# Pair_1.net
KiCad netlist of a schematic drawn in Altium Designer
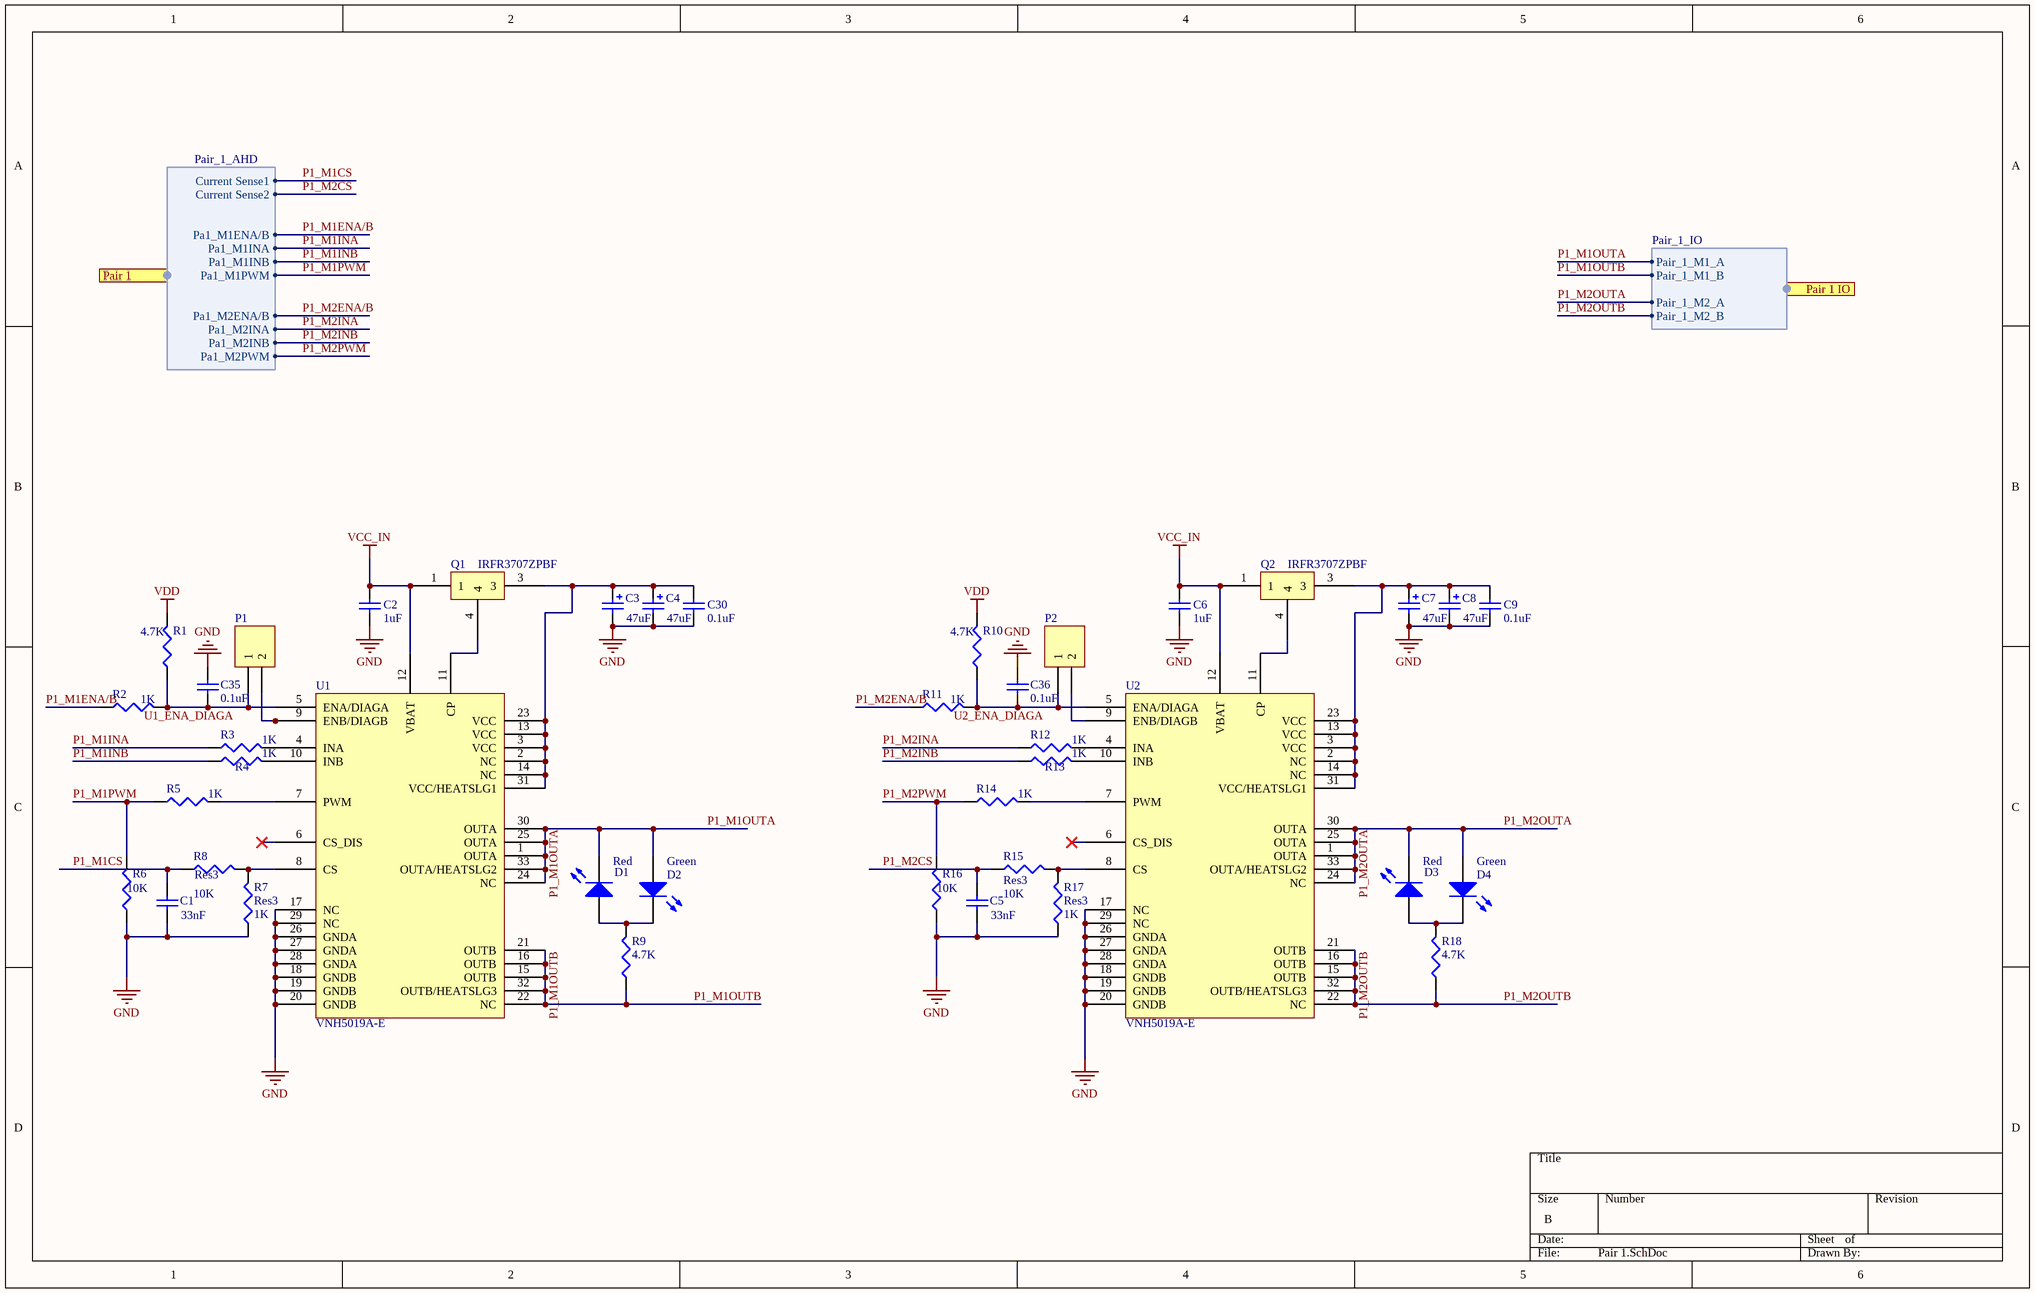
[diagram p0: Pair 1.SchDoc]

(export (version "E")
  (design (tool "Eeschema 10.0.6"))
  (components
    (comp (ref "C1")
      (value "33nF")
      (footprint "1608[0603]")
      (description "Capacitor (Semiconductor SIM Model)")
      (fields (field (name "Comment") "Cap Semi") (field (name "PUBLISHER") "Altium Limited"))
      (libsource (lib "Miscellaneous Devices") (part "Cap Semi"))
    )
    (comp (ref "C2")
      (value "1uF")
      (footprint "1608[0603]")
      (description "Capacitor (Semiconductor SIM Model)")
      (fields (field (name "Comment") "Cap Semi") (field (name "PUBLISHER") "Altium Limited"))
      (libsource (lib "Miscellaneous Devices") (part "Cap Semi"))
    )
    (comp (ref "C3")
      (value "47uF")
      (footprint "CAPPR2-5x6.8")
      (description "Polarized Capacitor (Axial)")
      (fields (field (name "Comment") "Cap Pol2") (field (name "PUBLISHER") "Altium Limited"))
      (libsource (lib "Miscellaneous Devices") (part "Cap Pol2"))
    )
    (comp (ref "C4")
      (value "47uF")
      (footprint "CAPPR2-5x6.8")
      (description "Polarized Capacitor (Axial)")
      (fields (field (name "Comment") "Cap Pol2") (field (name "PUBLISHER") "Altium Limited"))
      (libsource (lib "Miscellaneous Devices") (part "Cap Pol2"))
    )
    (comp (ref "C5")
      (value "33nF")
      (footprint "1608[0603]")
      (description "Capacitor (Semiconductor SIM Model)")
      (fields (field (name "Comment") "Cap Semi") (field (name "PUBLISHER") "Altium Limited"))
      (libsource (lib "Miscellaneous Devices") (part "Cap Semi"))
    )
    (comp (ref "C6")
      (value "1uF")
      (footprint "1608[0603]")
      (description "Capacitor (Semiconductor SIM Model)")
      (fields (field (name "Comment") "Cap Semi") (field (name "PUBLISHER") "Altium Limited"))
      (libsource (lib "Miscellaneous Devices") (part "Cap Semi"))
    )
    (comp (ref "C7")
      (value "47uF")
      (footprint "CAPPR2-5x6.8")
      (description "Polarized Capacitor (Axial)")
      (fields (field (name "Comment") "Cap Pol2") (field (name "PUBLISHER") "Altium Limited"))
      (libsource (lib "Miscellaneous Devices") (part "Cap Pol2"))
    )
    (comp (ref "C8")
      (value "47uF")
      (footprint "CAPPR2-5x6.8")
      (description "Polarized Capacitor (Axial)")
      (fields (field (name "Comment") "Cap Pol2") (field (name "PUBLISHER") "Altium Limited"))
      (libsource (lib "Miscellaneous Devices") (part "Cap Pol2"))
    )
    (comp (ref "C9")
      (value "0.1uF")
      (footprint "C1206")
      (description "Capacitor (Semiconductor SIM Model)")
      (fields (field (name "Comment") "Cap Semi") (field (name "PUBLISHER") "Altium Limited"))
      (libsource (lib "Miscellaneous Devices") (part "Cap Semi"))
    )
    (comp (ref "C30")
      (value "0.1uF")
      (footprint "C1206")
      (description "Capacitor (Semiconductor SIM Model)")
      (fields (field (name "Comment") "Cap Semi") (field (name "PUBLISHER") "Altium Limited"))
      (libsource (lib "Miscellaneous Devices") (part "Cap Semi"))
    )
    (comp (ref "C35")
      (value "0.1uF")
      (footprint "1608[0603]")
      (description "Capacitor (Semiconductor SIM Model)")
      (fields (field (name "Comment") "Cap Semi") (field (name "PUBLISHER") "Altium Limited"))
      (libsource (lib "Miscellaneous Devices") (part "Cap Semi"))
    )
    (comp (ref "C36")
      (value "0.1uF")
      (footprint "1608[0603]")
      (description "Capacitor (Semiconductor SIM Model)")
      (fields (field (name "Comment") "Cap Semi") (field (name "PUBLISHER") "Altium Limited"))
      (libsource (lib "Miscellaneous Devices") (part "Cap Semi"))
    )
    (comp (ref "D1")
      (value "LED2")
      (footprint "3.2X1.6X1.1")
      (description "Typical RED, GREEN, YELLOW, AMBER GaAs LED")
      (fields (field (name "PUBLISHER") "Altium Limited"))
      (libsource (lib "Miscellaneous Devices") (part "LED2"))
    )
    (comp (ref "D2")
      (value "LED2")
      (footprint "3.2X1.6X1.1")
      (description "Typical RED, GREEN, YELLOW, AMBER GaAs LED")
      (fields (field (name "PUBLISHER") "Altium Limited"))
      (libsource (lib "Miscellaneous Devices") (part "LED2"))
    )
    (comp (ref "D3")
      (value "LED2")
      (footprint "3.2X1.6X1.1")
      (description "Typical RED, GREEN, YELLOW, AMBER GaAs LED")
      (fields (field (name "PUBLISHER") "Altium Limited"))
      (libsource (lib "Miscellaneous Devices") (part "LED2"))
    )
    (comp (ref "D4")
      (value "LED2")
      (footprint "3.2X1.6X1.1")
      (description "Typical RED, GREEN, YELLOW, AMBER GaAs LED")
      (fields (field (name "PUBLISHER") "Altium Limited"))
      (libsource (lib "Miscellaneous Devices") (part "LED2"))
    )
    (comp (ref "P1")
      (value "Header 2")
      (footprint "HDR1X2")
      (description "Header, 2-Pin")
      (fields (field (name "PUBLISHER") "Altium Limited"))
      (libsource (lib "Miscellaneous Connectors") (part "Header 2"))
    )
    (comp (ref "P2")
      (value "Header 2")
      (footprint "HDR1X2")
      (description "Header, 2-Pin")
      (fields (field (name "PUBLISHER") "Altium Limited"))
      (libsource (lib "Miscellaneous Connectors") (part "Header 2"))
    )
    (comp (ref "Q1")
      (value "IRFR3707ZPBF")
      (footprint "IRFR3707ZPBF")
      (description "Power FET")
      (libsource (lib "Thruster Shield Part Library") (part "IRFR3707ZPBF"))
    )
    (comp (ref "Q2")
      (value "IRFR3707ZPBF")
      (footprint "IRFR3707ZPBF")
      (description "Power FET")
      (libsource (lib "Thruster Shield Part Library") (part "IRFR3707ZPBF"))
    )
    (comp (ref "R1")
      (value "4.7K")
      (footprint "RESC1608L")
      (description "Resistor")
      (fields (field (name "Comment") "Res3") (field (name "PUBLISHER") "Altium Limited"))
      (libsource (lib "Miscellaneous Devices") (part "Res3"))
    )
    (comp (ref "R2")
      (value "1K")
      (footprint "RESC1608L")
      (description "Resistor")
      (fields (field (name "Comment") "Res3") (field (name "PUBLISHER") "Altium Limited"))
      (libsource (lib "Miscellaneous Devices") (part "Res3"))
    )
    (comp (ref "R3")
      (value "1K")
      (footprint "RESC1608L")
      (description "Resistor")
      (fields (field (name "Comment") "Res3") (field (name "PUBLISHER") "Altium Limited"))
      (libsource (lib "Miscellaneous Devices") (part "Res3"))
    )
    (comp (ref "R4")
      (value "1K")
      (footprint "RESC1608L")
      (description "Resistor")
      (fields (field (name "Comment") "Res3") (field (name "PUBLISHER") "Altium Limited"))
      (libsource (lib "Miscellaneous Devices") (part "Res3"))
    )
    (comp (ref "R5")
      (value "1K")
      (footprint "RESC1608L")
      (description "Resistor")
      (fields (field (name "Comment") "Res3") (field (name "PUBLISHER") "Altium Limited"))
      (libsource (lib "Miscellaneous Devices") (part "Res3"))
    )
    (comp (ref "R6")
      (value "10K")
      (footprint "RESC1608L")
      (description "Resistor")
      (fields (field (name "Comment") "Res3") (field (name "PUBLISHER") "Altium Limited"))
      (libsource (lib "Miscellaneous Devices") (part "Res3"))
    )
    (comp (ref "R7")
      (value "Res3")
      (footprint "RESC1608L")
      (description "Resistor")
      (fields (field (name "ALTIUM_VALUE") "1K") (field (name "PUBLISHER") "Altium Limited"))
      (libsource (lib "Miscellaneous Devices") (part "Res3"))
    )
    (comp (ref "R8")
      (value "Res3")
      (footprint "RESC1608L")
      (description "Resistor")
      (fields (field (name "ALTIUM_VALUE") "10K") (field (name "PUBLISHER") "Altium Limited"))
      (libsource (lib "Miscellaneous Devices") (part "Res3"))
    )
    (comp (ref "R9")
      (value "4.7K")
      (footprint "0805 SMD Resistor")
      (description "Resistor")
      (fields (field (name "Comment") "Res3") (field (name "PUBLISHER") "Altium Limited"))
      (libsource (lib "Miscellaneous Devices") (part "Res3"))
    )
    (comp (ref "R10")
      (value "4.7K")
      (footprint "RESC1608L")
      (description "Resistor")
      (fields (field (name "Comment") "Res3") (field (name "PUBLISHER") "Altium Limited"))
      (libsource (lib "Miscellaneous Devices") (part "Res3"))
    )
    (comp (ref "R11")
      (value "1K")
      (footprint "RESC1608L")
      (description "Resistor")
      (fields (field (name "Comment") "Res3") (field (name "PUBLISHER") "Altium Limited"))
      (libsource (lib "Miscellaneous Devices") (part "Res3"))
    )
    (comp (ref "R12")
      (value "1K")
      (footprint "RESC1608L")
      (description "Resistor")
      (fields (field (name "Comment") "Res3") (field (name "PUBLISHER") "Altium Limited"))
      (libsource (lib "Miscellaneous Devices") (part "Res3"))
    )
    (comp (ref "R13")
      (value "1K")
      (footprint "RESC1608L")
      (description "Resistor")
      (fields (field (name "Comment") "Res3") (field (name "PUBLISHER") "Altium Limited"))
      (libsource (lib "Miscellaneous Devices") (part "Res3"))
    )
    (comp (ref "R14")
      (value "1K")
      (footprint "RESC1608L")
      (description "Resistor")
      (fields (field (name "Comment") "Res3") (field (name "PUBLISHER") "Altium Limited"))
      (libsource (lib "Miscellaneous Devices") (part "Res3"))
    )
    (comp (ref "R15")
      (value "Res3")
      (footprint "RESC1608L")
      (description "Resistor")
      (fields (field (name "ALTIUM_VALUE") "10K") (field (name "PUBLISHER") "Altium Limited"))
      (libsource (lib "Miscellaneous Devices") (part "Res3"))
    )
    (comp (ref "R16")
      (value "10K")
      (footprint "RESC1608L")
      (description "Resistor")
      (fields (field (name "Comment") "Res3") (field (name "PUBLISHER") "Altium Limited"))
      (libsource (lib "Miscellaneous Devices") (part "Res3"))
    )
    (comp (ref "R17")
      (value "Res3")
      (footprint "RESC1608L")
      (description "Resistor")
      (fields (field (name "ALTIUM_VALUE") "1K") (field (name "PUBLISHER") "Altium Limited"))
      (libsource (lib "Miscellaneous Devices") (part "Res3"))
    )
    (comp (ref "R18")
      (value "4.7K")
      (footprint "0805 SMD Resistor")
      (description "Resistor")
      (fields (field (name "Comment") "Res3") (field (name "PUBLISHER") "Altium Limited"))
      (libsource (lib "Miscellaneous Devices") (part "Res3"))
    )
    (comp (ref "U1")
      (value "VNH5019A-E")
      (footprint "VNH5019A-E")
      (description "VNH5019A-E H-Bridge")
      (libsource (lib "Thruster Shield Part Library") (part "VNH5019A-E"))
    )
    (comp (ref "U2")
      (value "VNH5019A-E")
      (footprint "VNH5019A-E")
      (description "VNH5019A-E H-Bridge")
      (libsource (lib "Thruster Shield Part Library") (part "VNH5019A-E"))
    )
  )
  (nets
    (net (code "3") (name "/P1_M1CS") (class "Default")
      (node (ref "C1") (pin "2") (pinfunction "2_2") (pintype "passive"))
      (node (ref "R8") (pin "1") (pinfunction "1_1") (pintype "passive"))
    )
    (net (code "4") (name "/P1_M1ENA{slash}B") (class "Default")
      (node (ref "R2") (pin "1") (pinfunction "1_1") (pintype "passive"))
    )
    (net (code "5") (name "/P1_M1INA") (class "Default")
      (node (ref "R3") (pin "1") (pinfunction "1_1") (pintype "passive"))
    )
    (net (code "6") (name "/P1_M1INB") (class "Default")
      (node (ref "R4") (pin "1") (pinfunction "1_1") (pintype "passive"))
    )
    (net (code "7") (name "/P1_M1OUTA") (class "Default")
      (node (ref "D1") (pin "2") (pinfunction "K_2") (pintype "passive"))
      (node (ref "D2") (pin "1") (pinfunction "A_1") (pintype "passive"))
      (node (ref "U1") (pin "1") (pinfunction "OUTA_1") (pintype "passive"))
      (node (ref "U1") (pin "24") (pinfunction "NC_24") (pintype "passive"))
      (node (ref "U1") (pin "25") (pinfunction "OUTA_25") (pintype "passive"))
      (node (ref "U1") (pin "30") (pinfunction "OUTA_30") (pintype "passive"))
      (node (ref "U1") (pin "33") (pinfunction "OUTA/HEATSLG2_33") (pintype "passive"))
    )
    (net (code "8") (name "/P1_M1OUTB") (class "Default")
      (node (ref "R9") (pin "1") (pinfunction "1_1") (pintype "passive"))
      (node (ref "U1") (pin "15") (pinfunction "OUTB_15") (pintype "passive"))
      (node (ref "U1") (pin "16") (pinfunction "OUTB_16") (pintype "passive"))
      (node (ref "U1") (pin "21") (pinfunction "OUTB_21") (pintype "passive"))
      (node (ref "U1") (pin "22") (pinfunction "NC_22") (pintype "passive"))
      (node (ref "U1") (pin "32") (pinfunction "OUTB/HEATSLG3_32") (pintype "passive"))
    )
    (net (code "9") (name "/P1_M1PWM") (class "Default")
      (node (ref "R5") (pin "1") (pinfunction "1_1") (pintype "passive"))
      (node (ref "R6") (pin "2") (pinfunction "2_2") (pintype "passive"))
    )
    (net (code "10") (name "/P1_M2CS") (class "Default")
      (node (ref "C5") (pin "2") (pinfunction "2_2") (pintype "passive"))
      (node (ref "R15") (pin "1") (pinfunction "1_1") (pintype "passive"))
    )
    (net (code "11") (name "/P1_M2ENA{slash}B") (class "Default")
      (node (ref "R11") (pin "1") (pinfunction "1_1") (pintype "passive"))
    )
    (net (code "12") (name "/P1_M2INA") (class "Default")
      (node (ref "R12") (pin "1") (pinfunction "1_1") (pintype "passive"))
    )
    (net (code "13") (name "/P1_M2INB") (class "Default")
      (node (ref "R13") (pin "1") (pinfunction "1_1") (pintype "passive"))
    )
    (net (code "14") (name "/P1_M2OUTA") (class "Default")
      (node (ref "D3") (pin "2") (pinfunction "K_2") (pintype "passive"))
      (node (ref "D4") (pin "1") (pinfunction "A_1") (pintype "passive"))
      (node (ref "U2") (pin "1") (pinfunction "OUTA_1") (pintype "passive"))
      (node (ref "U2") (pin "24") (pinfunction "NC_24") (pintype "passive"))
      (node (ref "U2") (pin "25") (pinfunction "OUTA_25") (pintype "passive"))
      (node (ref "U2") (pin "30") (pinfunction "OUTA_30") (pintype "passive"))
      (node (ref "U2") (pin "33") (pinfunction "OUTA/HEATSLG2_33") (pintype "passive"))
    )
    (net (code "15") (name "/P1_M2OUTB") (class "Default")
      (node (ref "R18") (pin "1") (pinfunction "1_1") (pintype "passive"))
      (node (ref "U2") (pin "15") (pinfunction "OUTB_15") (pintype "passive"))
      (node (ref "U2") (pin "16") (pinfunction "OUTB_16") (pintype "passive"))
      (node (ref "U2") (pin "21") (pinfunction "OUTB_21") (pintype "passive"))
      (node (ref "U2") (pin "22") (pinfunction "NC_22") (pintype "passive"))
      (node (ref "U2") (pin "32") (pinfunction "OUTB/HEATSLG3_32") (pintype "passive"))
    )
    (net (code "16") (name "/P1_M2PWM") (class "Default")
      (node (ref "R14") (pin "1") (pinfunction "1_1") (pintype "passive"))
      (node (ref "R16") (pin "2") (pinfunction "2_2") (pintype "passive"))
    )
    (net (code "17") (name "/U1_ENA_DIAGA") (class "Default")
      (node (ref "C35") (pin "2") (pinfunction "2_2") (pintype "passive"))
      (node (ref "P1") (pin "1") (pinfunction "1_1") (pintype "passive"))
      (node (ref "R1") (pin "1") (pinfunction "1_1") (pintype "passive"))
      (node (ref "R2") (pin "2") (pinfunction "2_2") (pintype "passive"))
      (node (ref "U1") (pin "5") (pinfunction "ENA/DIAGA_5") (pintype "passive"))
    )
    (net (code "18") (name "/U2_ENA_DIAGA") (class "Default")
      (node (ref "C36") (pin "2") (pinfunction "2_2") (pintype "passive"))
      (node (ref "P2") (pin "1") (pinfunction "1_1") (pintype "passive"))
      (node (ref "R10") (pin "1") (pinfunction "1_1") (pintype "passive"))
      (node (ref "R11") (pin "2") (pinfunction "2_2") (pintype "passive"))
      (node (ref "U2") (pin "5") (pinfunction "ENA/DIAGA_5") (pintype "passive"))
    )
    (net (code "21") (name "GND") (class "Default")
      (node (ref "C1") (pin "1") (pinfunction "1_1") (pintype "passive"))
      (node (ref "C2") (pin "1") (pinfunction "1_1") (pintype "passive"))
      (node (ref "C3") (pin "2") (pinfunction "2_2") (pintype "passive"))
      (node (ref "C30") (pin "1") (pinfunction "1_1") (pintype "passive"))
      (node (ref "C35") (pin "1") (pinfunction "1_1") (pintype "passive"))
      (node (ref "C36") (pin "1") (pinfunction "1_1") (pintype "passive"))
      (node (ref "C4") (pin "2") (pinfunction "2_2") (pintype "passive"))
      (node (ref "C5") (pin "1") (pinfunction "1_1") (pintype "passive"))
      (node (ref "C6") (pin "1") (pinfunction "1_1") (pintype "passive"))
      (node (ref "C7") (pin "2") (pinfunction "2_2") (pintype "passive"))
      (node (ref "C8") (pin "2") (pinfunction "2_2") (pintype "passive"))
      (node (ref "C9") (pin "1") (pinfunction "1_1") (pintype "passive"))
      (node (ref "R16") (pin "1") (pinfunction "1_1") (pintype "passive"))
      (node (ref "R17") (pin "1") (pinfunction "1_1") (pintype "passive"))
      (node (ref "R6") (pin "1") (pinfunction "1_1") (pintype "passive"))
      (node (ref "R7") (pin "1") (pinfunction "1_1") (pintype "passive"))
      (node (ref "U1") (pin "17") (pinfunction "NC_17") (pintype "passive"))
      (node (ref "U1") (pin "18") (pinfunction "GNDB_18") (pintype "passive"))
      (node (ref "U1") (pin "19") (pinfunction "GNDB_19") (pintype "passive"))
      (node (ref "U1") (pin "20") (pinfunction "GNDB_20") (pintype "passive"))
      (node (ref "U1") (pin "26") (pinfunction "GNDA_26") (pintype "passive"))
      (node (ref "U1") (pin "27") (pinfunction "GNDA_27") (pintype "passive"))
      (node (ref "U1") (pin "28") (pinfunction "GNDA_28") (pintype "passive"))
      (node (ref "U1") (pin "29") (pinfunction "NC_29") (pintype "passive"))
      (node (ref "U2") (pin "17") (pinfunction "NC_17") (pintype "passive"))
      (node (ref "U2") (pin "18") (pinfunction "GNDB_18") (pintype "passive"))
      (node (ref "U2") (pin "19") (pinfunction "GNDB_19") (pintype "passive"))
      (node (ref "U2") (pin "20") (pinfunction "GNDB_20") (pintype "passive"))
      (node (ref "U2") (pin "26") (pinfunction "GNDA_26") (pintype "passive"))
      (node (ref "U2") (pin "27") (pinfunction "GNDA_27") (pintype "passive"))
      (node (ref "U2") (pin "28") (pinfunction "GNDA_28") (pintype "passive"))
      (node (ref "U2") (pin "29") (pinfunction "NC_29") (pintype "passive"))
    )
    (net (code "22") (name "Net-(D1-A)") (class "Default")
      (node (ref "D1") (pin "1") (pinfunction "A_1") (pintype "passive"))
      (node (ref "D2") (pin "2") (pinfunction "K_2") (pintype "passive"))
      (node (ref "R9") (pin "2") (pinfunction "2_2") (pintype "passive"))
    )
    (net (code "23") (name "Net-(D3-A)") (class "Default")
      (node (ref "D3") (pin "1") (pinfunction "A_1") (pintype "passive"))
      (node (ref "D4") (pin "2") (pinfunction "K_2") (pintype "passive"))
      (node (ref "R18") (pin "2") (pinfunction "2_2") (pintype "passive"))
    )
    (net (code "24") (name "Net-(U1-CP)") (class "Default")
      (node (ref "Q1") (pin "4") (pinfunction "4_4") (pintype "passive"))
      (node (ref "U1") (pin "11") (pinfunction "CP_11") (pintype "passive"))
    )
    (net (code "25") (name "Net-(U1-CS)") (class "Default")
      (node (ref "R7") (pin "2") (pinfunction "2_2") (pintype "passive"))
      (node (ref "R8") (pin "2") (pinfunction "2_2") (pintype "passive"))
      (node (ref "U1") (pin "8") (pinfunction "CS_8") (pintype "passive"))
    )
    (net (code "26") (name "Net-(U1-ENB{slash}DIAGB)") (class "Default")
      (node (ref "P1") (pin "2") (pinfunction "2_2") (pintype "passive"))
      (node (ref "U1") (pin "9") (pinfunction "ENB/DIAGB_9") (pintype "passive"))
    )
    (net (code "27") (name "Net-(U1-INA)") (class "Default")
      (node (ref "R3") (pin "2") (pinfunction "2_2") (pintype "passive"))
      (node (ref "U1") (pin "4") (pinfunction "INA_4") (pintype "passive"))
    )
    (net (code "28") (name "Net-(U1-INB)") (class "Default")
      (node (ref "R4") (pin "2") (pinfunction "2_2") (pintype "passive"))
      (node (ref "U1") (pin "10") (pinfunction "INB_10") (pintype "passive"))
    )
    (net (code "29") (name "Net-(U1-PWM)") (class "Default")
      (node (ref "R5") (pin "2") (pinfunction "2_2") (pintype "passive"))
      (node (ref "U1") (pin "7") (pinfunction "PWM_7") (pintype "passive"))
    )
    (net (code "30") (name "Net-(U1-VCC{slash}HEATSLG1)") (class "Default")
      (node (ref "C3") (pin "1") (pinfunction "1_1") (pintype "passive"))
      (node (ref "C30") (pin "2") (pinfunction "2_2") (pintype "passive"))
      (node (ref "C4") (pin "1") (pinfunction "1_1") (pintype "passive"))
      (node (ref "Q1") (pin "3") (pinfunction "3_3") (pintype "passive"))
      (node (ref "U1") (pin "13") (pinfunction "VCC_13") (pintype "passive"))
      (node (ref "U1") (pin "14") (pinfunction "NC_14") (pintype "passive"))
      (node (ref "U1") (pin "2") (pinfunction "NC_2") (pintype "passive"))
      (node (ref "U1") (pin "23") (pinfunction "VCC_23") (pintype "passive"))
      (node (ref "U1") (pin "3") (pinfunction "VCC_3") (pintype "passive"))
      (node (ref "U1") (pin "31") (pinfunction "VCC/HEATSLG1_31") (pintype "passive"))
    )
    (net (code "31") (name "Net-(U2-CP)") (class "Default")
      (node (ref "Q2") (pin "4") (pinfunction "4_4") (pintype "passive"))
      (node (ref "U2") (pin "11") (pinfunction "CP_11") (pintype "passive"))
    )
    (net (code "32") (name "Net-(U2-CS)") (class "Default")
      (node (ref "R15") (pin "2") (pinfunction "2_2") (pintype "passive"))
      (node (ref "R17") (pin "2") (pinfunction "2_2") (pintype "passive"))
      (node (ref "U2") (pin "8") (pinfunction "CS_8") (pintype "passive"))
    )
    (net (code "33") (name "Net-(U2-ENB{slash}DIAGB)") (class "Default")
      (node (ref "P2") (pin "2") (pinfunction "2_2") (pintype "passive"))
      (node (ref "U2") (pin "9") (pinfunction "ENB/DIAGB_9") (pintype "passive"))
    )
    (net (code "34") (name "Net-(U2-INA)") (class "Default")
      (node (ref "R12") (pin "2") (pinfunction "2_2") (pintype "passive"))
      (node (ref "U2") (pin "4") (pinfunction "INA_4") (pintype "passive"))
    )
    (net (code "35") (name "Net-(U2-INB)") (class "Default")
      (node (ref "R13") (pin "2") (pinfunction "2_2") (pintype "passive"))
      (node (ref "U2") (pin "10") (pinfunction "INB_10") (pintype "passive"))
    )
    (net (code "36") (name "Net-(U2-PWM)") (class "Default")
      (node (ref "R14") (pin "2") (pinfunction "2_2") (pintype "passive"))
      (node (ref "U2") (pin "7") (pinfunction "PWM_7") (pintype "passive"))
    )
    (net (code "37") (name "Net-(U2-VCC{slash}HEATSLG1)") (class "Default")
      (node (ref "C7") (pin "1") (pinfunction "1_1") (pintype "passive"))
      (node (ref "C8") (pin "1") (pinfunction "1_1") (pintype "passive"))
      (node (ref "C9") (pin "2") (pinfunction "2_2") (pintype "passive"))
      (node (ref "Q2") (pin "3") (pinfunction "3_3") (pintype "passive"))
      (node (ref "U2") (pin "13") (pinfunction "VCC_13") (pintype "passive"))
      (node (ref "U2") (pin "14") (pinfunction "NC_14") (pintype "passive"))
      (node (ref "U2") (pin "2") (pinfunction "NC_2") (pintype "passive"))
      (node (ref "U2") (pin "23") (pinfunction "VCC_23") (pintype "passive"))
      (node (ref "U2") (pin "3") (pinfunction "VCC_3") (pintype "passive"))
      (node (ref "U2") (pin "31") (pinfunction "VCC/HEATSLG1_31") (pintype "passive"))
    )
    (net (code "38") (name "VCC_IN") (class "Default")
      (node (ref "C2") (pin "2") (pinfunction "2_2") (pintype "passive"))
      (node (ref "C6") (pin "2") (pinfunction "2_2") (pintype "passive"))
      (node (ref "Q1") (pin "1") (pinfunction "1_1") (pintype "passive"))
      (node (ref "Q2") (pin "1") (pinfunction "1_1") (pintype "passive"))
      (node (ref "U1") (pin "12") (pinfunction "VBAT_12") (pintype "passive"))
      (node (ref "U2") (pin "12") (pinfunction "VBAT_12") (pintype "passive"))
    )
    (net (code "39") (name "VDD") (class "Default")
      (node (ref "R1") (pin "2") (pinfunction "2_2") (pintype "passive"))
      (node (ref "R10") (pin "2") (pinfunction "2_2") (pintype "passive"))
    )
    (net (code "40") (name "unconnected-(U1-CS_DIS-Pad6)") (class "Default")
      (node (ref "U1") (pin "6") (pinfunction "CS_DIS_6") (pintype "passive+no_connect"))
    )
    (net (code "41") (name "unconnected-(U2-CS_DIS-Pad6)") (class "Default")
      (node (ref "U2") (pin "6") (pinfunction "CS_DIS_6") (pintype "passive+no_connect"))
    )
  )
)
